# MTR_1_0.net
KiCad netlist of a schematic drawn in EAGLE
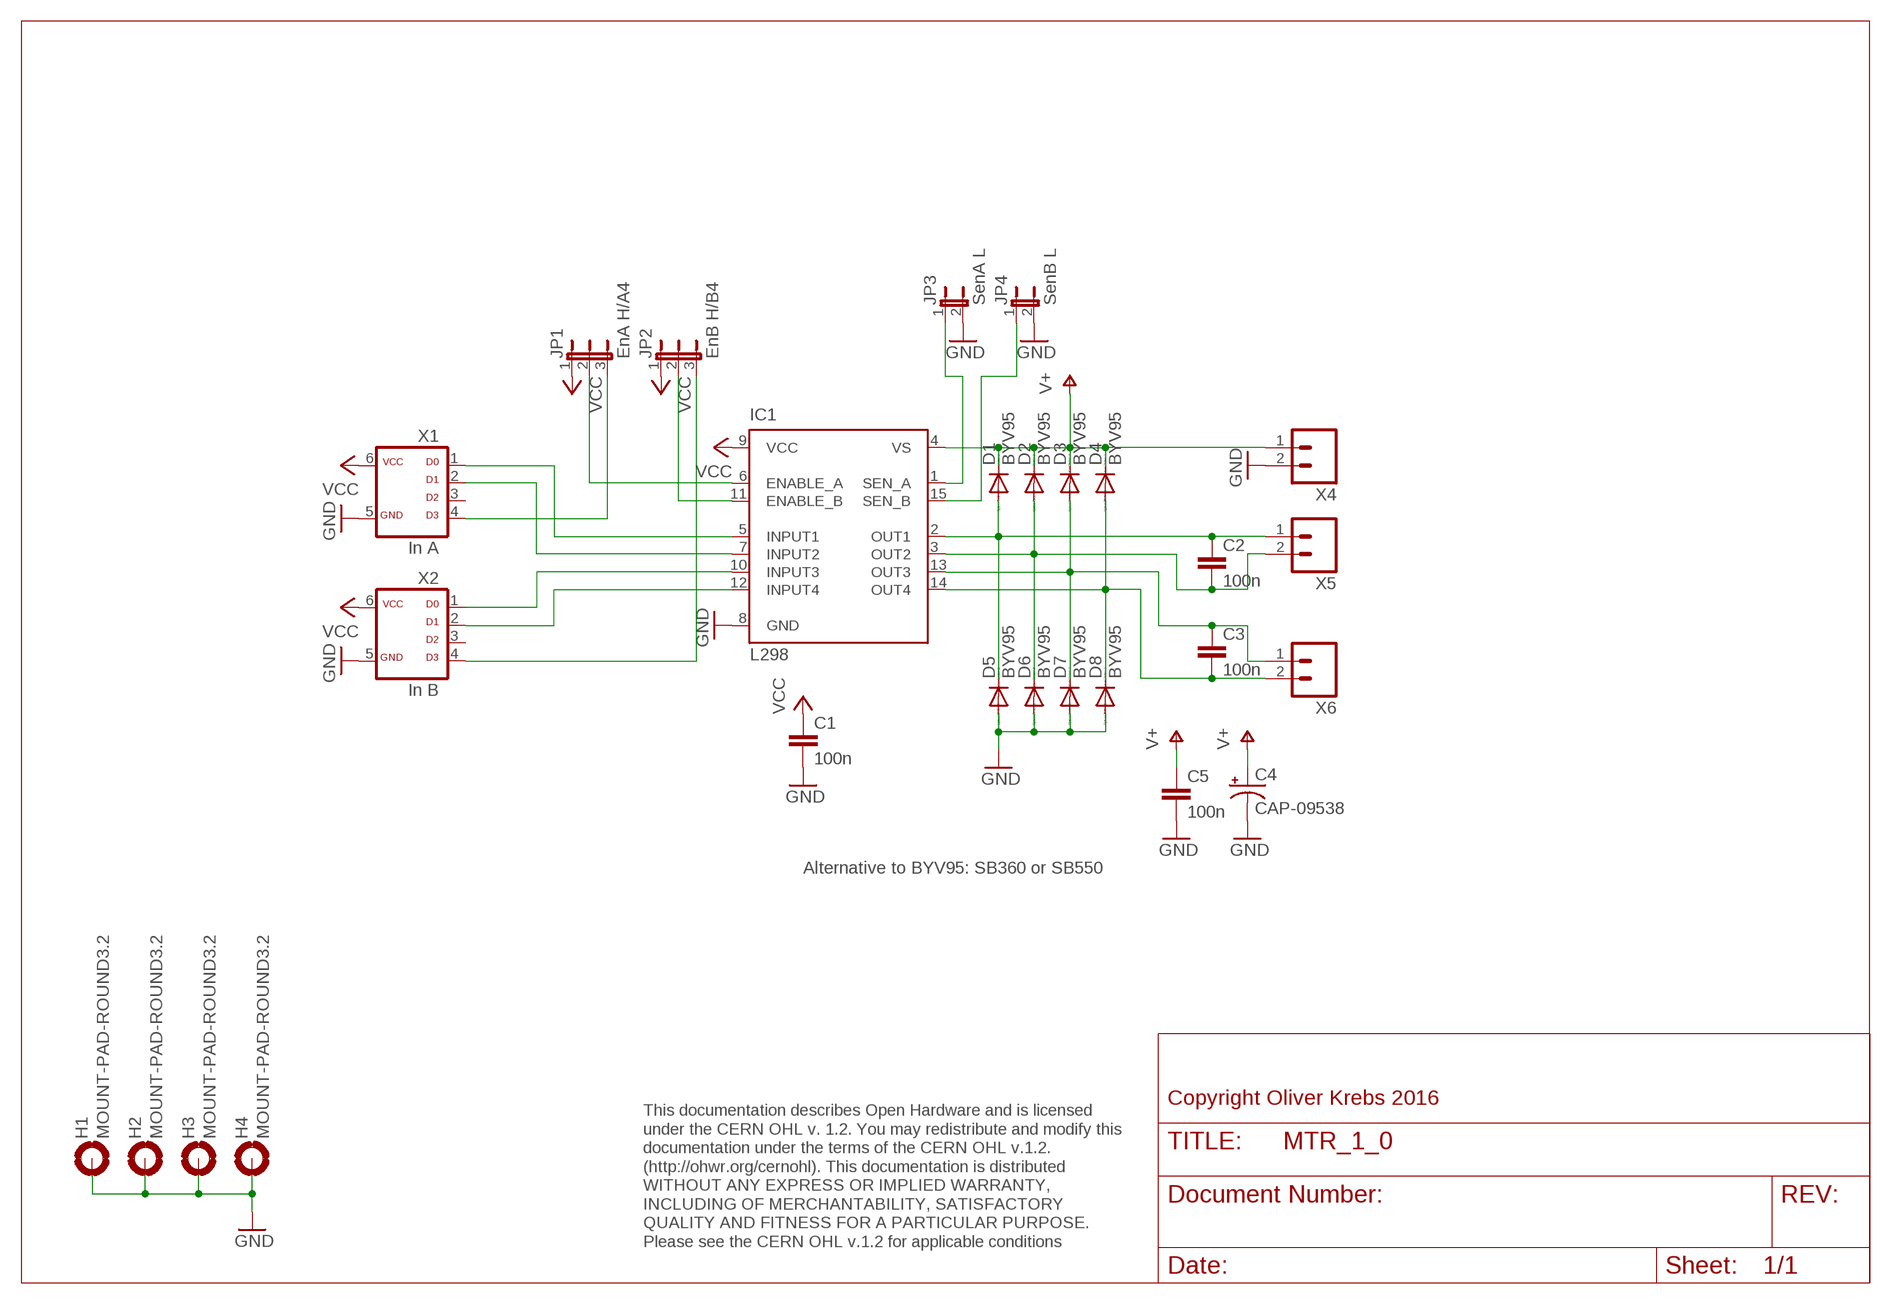
[diagram p0: schematic, sheet 1]

(export (version "E")
  (design (tool "Eeschema 10.0.6"))
  (components
    (comp (ref "C1")
      (value "100n")
      (footprint "eagle-import:C050-025X075")
      (libsource (lib "eagle-import") (part "C-EU050-025X075"))
    )
    (comp (ref "C2")
      (value "100n")
      (footprint "eagle-import:C050-025X075")
      (libsource (lib "eagle-import") (part "C-EU050-025X075"))
    )
    (comp (ref "C3")
      (value "100n")
      (footprint "eagle-import:C050-025X075")
      (libsource (lib "eagle-import") (part "C-EU050-025X075"))
    )
    (comp (ref "C4")
      (value "CAP-09538")
      (footprint "eagle-import:CPOL-RADIAL-1000UF-25V")
      (libsource (lib "eagle-import") (part "1000UF-25V(PTH)"))
    )
    (comp (ref "C5")
      (value "100n")
      (footprint "eagle-import:C050-025X075")
      (libsource (lib "eagle-import") (part "C-EU050-025X075"))
    )
    (comp (ref "D1")
      (value "BYV95")
      (footprint "eagle-import:SOD57-10")
      (libsource (lib "eagle-import") (part "BYV95"))
    )
    (comp (ref "D2")
      (value "BYV95")
      (footprint "eagle-import:SOD57-10")
      (libsource (lib "eagle-import") (part "BYV95"))
    )
    (comp (ref "D3")
      (value "BYV95")
      (footprint "eagle-import:SOD57-10")
      (libsource (lib "eagle-import") (part "BYV95"))
    )
    (comp (ref "D4")
      (value "BYV95")
      (footprint "eagle-import:SOD57-10")
      (libsource (lib "eagle-import") (part "BYV95"))
    )
    (comp (ref "D5")
      (value "BYV95")
      (footprint "eagle-import:SOD57-10")
      (libsource (lib "eagle-import") (part "BYV95"))
    )
    (comp (ref "D6")
      (value "BYV95")
      (footprint "eagle-import:SOD57-10")
      (libsource (lib "eagle-import") (part "BYV95"))
    )
    (comp (ref "D7")
      (value "BYV95")
      (footprint "eagle-import:SOD57-10")
      (libsource (lib "eagle-import") (part "BYV95"))
    )
    (comp (ref "D8")
      (value "BYV95")
      (footprint "eagle-import:SOD57-10")
      (libsource (lib "eagle-import") (part "BYV95"))
    )
    (comp (ref "H1")
      (value "MOUNT-PAD-ROUND3.2")
      (footprint "eagle-import:3,2-PAD")
      (libsource (lib "eagle-import") (part "MOUNT-PAD-ROUND3.2"))
    )
    (comp (ref "H2")
      (value "MOUNT-PAD-ROUND3.2")
      (footprint "eagle-import:3,2-PAD")
      (libsource (lib "eagle-import") (part "MOUNT-PAD-ROUND3.2"))
    )
    (comp (ref "H3")
      (value "MOUNT-PAD-ROUND3.2")
      (footprint "eagle-import:3,2-PAD")
      (libsource (lib "eagle-import") (part "MOUNT-PAD-ROUND3.2"))
    )
    (comp (ref "H4")
      (value "MOUNT-PAD-ROUND3.2")
      (footprint "eagle-import:3,2-PAD")
      (libsource (lib "eagle-import") (part "MOUNT-PAD-ROUND3.2"))
    )
    (comp (ref "IC1")
      (value "L298")
      (footprint "eagle-import:MULTIWATT-15")
      (fields (field (name "MPN") "L298N"))
      (libsource (lib "eagle-import") (part "L298"))
    )
    (comp (ref "JP1")
      (value "EnA H/A4")
      (footprint "eagle-import:JP2-U")
      (libsource (lib "eagle-import") (part "JP2EJP2-U"))
    )
    (comp (ref "JP2")
      (value "EnB H/B4")
      (footprint "eagle-import:JP2-U")
      (libsource (lib "eagle-import") (part "JP2EJP2-U"))
    )
    (comp (ref "JP3")
      (value "SenA L")
      (footprint "eagle-import:JP1")
      (libsource (lib "eagle-import") (part "JP1E"))
    )
    (comp (ref "JP4")
      (value "SenB L")
      (footprint "eagle-import:JP1")
      (libsource (lib "eagle-import") (part "JP1E"))
    )
    (comp (ref "X1")
      (value "In A")
      (footprint "eagle-import:ML-6")
      (libsource (lib "eagle-import") (part "ML6D"))
    )
    (comp (ref "X2")
      (value "In B")
      (footprint "eagle-import:ML-6")
      (libsource (lib "eagle-import") (part "ML6D"))
    )
    (comp (ref "X4")
      (value "M021.3MM-5.08")
      (footprint "eagle-import:1X02_BIG_5.08")
      (libsource (lib "eagle-import") (part "M021.3MM-5.08"))
    )
    (comp (ref "X5")
      (value "M021.3MM-5.08")
      (footprint "eagle-import:1X02_BIG_5.08")
      (libsource (lib "eagle-import") (part "M021.3MM-5.08"))
    )
    (comp (ref "X6")
      (value "M021.3MM-5.08")
      (footprint "eagle-import:1X02_BIG_5.08")
      (libsource (lib "eagle-import") (part "M021.3MM-5.08"))
    )
  )
  (nets
    (net (code "1") (name "GND") (class "Default")
      (node (ref "C1") (pin "2") (pinfunction "2_2") (pintype "passive"))
      (node (ref "C4") (pin "-") (pinfunction "-_-") (pintype "passive"))
      (node (ref "C5") (pin "2") (pinfunction "2_2") (pintype "passive"))
      (node (ref "D5") (pin "A") (pinfunction "A_A") (pintype "passive"))
      (node (ref "D6") (pin "A") (pinfunction "A_A") (pintype "passive"))
      (node (ref "D7") (pin "A") (pinfunction "A_A") (pintype "passive"))
      (node (ref "D8") (pin "A") (pinfunction "A_A") (pintype "passive"))
      (node (ref "H1") (pin "B3,2") (pinfunction "MOUNT_B3,2") (pintype "passive"))
      (node (ref "H2") (pin "B3,2") (pinfunction "MOUNT_B3,2") (pintype "passive"))
      (node (ref "H3") (pin "B3,2") (pinfunction "MOUNT_B3,2") (pintype "passive"))
      (node (ref "H4") (pin "B3,2") (pinfunction "MOUNT_B3,2") (pintype "passive"))
      (node (ref "IC1") (pin "8") (pinfunction "GND_8") (pintype "power_in"))
      (node (ref "JP3") (pin "2") (pinfunction "2_2") (pintype "passive"))
      (node (ref "JP4") (pin "2") (pinfunction "2_2") (pintype "passive"))
      (node (ref "X1") (pin "5") (pinfunction "5_5") (pintype "passive"))
      (node (ref "X2") (pin "5") (pinfunction "5_5") (pintype "passive"))
      (node (ref "X4") (pin "2") (pinfunction "2_2") (pintype "passive"))
    )
    (net (code "2") (name "Net-(IC1-ENABLE_A)") (class "Default")
      (node (ref "IC1") (pin "6") (pinfunction "ENABLE_A_6") (pintype "input"))
      (node (ref "JP1") (pin "2") (pinfunction "2_2") (pintype "passive"))
    )
    (net (code "3") (name "Net-(IC1-ENABLE_B)") (class "Default")
      (node (ref "IC1") (pin "11") (pinfunction "ENABLE_B_11") (pintype "input"))
      (node (ref "JP2") (pin "2") (pinfunction "2_2") (pintype "passive"))
    )
    (net (code "4") (name "Net-(IC1-INPUT1)") (class "Default")
      (node (ref "IC1") (pin "5") (pinfunction "INPUT1_5") (pintype "input"))
      (node (ref "X1") (pin "1") (pinfunction "1_1") (pintype "passive"))
    )
    (net (code "5") (name "Net-(IC1-INPUT2)") (class "Default")
      (node (ref "IC1") (pin "7") (pinfunction "INPUT2_7") (pintype "input"))
      (node (ref "X1") (pin "2") (pinfunction "2_2") (pintype "passive"))
    )
    (net (code "6") (name "Net-(IC1-INPUT3)") (class "Default")
      (node (ref "IC1") (pin "10") (pinfunction "INPUT3_10") (pintype "input"))
      (node (ref "X2") (pin "1") (pinfunction "1_1") (pintype "passive"))
    )
    (net (code "7") (name "Net-(IC1-INPUT4)") (class "Default")
      (node (ref "IC1") (pin "12") (pinfunction "INPUT4_12") (pintype "input"))
      (node (ref "X2") (pin "2") (pinfunction "2_2") (pintype "passive"))
    )
    (net (code "8") (name "Net-(IC1-OUT1)") (class "Default")
      (node (ref "C2") (pin "1") (pinfunction "1_1") (pintype "passive"))
      (node (ref "D1") (pin "A") (pinfunction "A_A") (pintype "passive"))
      (node (ref "D5") (pin "C") (pinfunction "C_C") (pintype "passive"))
      (node (ref "IC1") (pin "2") (pinfunction "OUT1_2") (pintype "output"))
      (node (ref "X5") (pin "1") (pinfunction "1_1") (pintype "passive"))
    )
    (net (code "9") (name "Net-(IC1-OUT2)") (class "Default")
      (node (ref "C2") (pin "2") (pinfunction "2_2") (pintype "passive"))
      (node (ref "D2") (pin "A") (pinfunction "A_A") (pintype "passive"))
      (node (ref "D6") (pin "C") (pinfunction "C_C") (pintype "passive"))
      (node (ref "IC1") (pin "3") (pinfunction "OUT2_3") (pintype "output"))
      (node (ref "X5") (pin "2") (pinfunction "2_2") (pintype "passive"))
    )
    (net (code "10") (name "Net-(IC1-OUT3)") (class "Default")
      (node (ref "C3") (pin "1") (pinfunction "1_1") (pintype "passive"))
      (node (ref "D3") (pin "A") (pinfunction "A_A") (pintype "passive"))
      (node (ref "D7") (pin "C") (pinfunction "C_C") (pintype "passive"))
      (node (ref "IC1") (pin "13") (pinfunction "OUT3_13") (pintype "output"))
      (node (ref "X6") (pin "1") (pinfunction "1_1") (pintype "passive"))
    )
    (net (code "11") (name "Net-(IC1-OUT4)") (class "Default")
      (node (ref "C3") (pin "2") (pinfunction "2_2") (pintype "passive"))
      (node (ref "D4") (pin "A") (pinfunction "A_A") (pintype "passive"))
      (node (ref "D8") (pin "C") (pinfunction "C_C") (pintype "passive"))
      (node (ref "IC1") (pin "14") (pinfunction "OUT4_14") (pintype "output"))
      (node (ref "X6") (pin "2") (pinfunction "2_2") (pintype "passive"))
    )
    (net (code "12") (name "Net-(IC1-SEN_A)") (class "Default")
      (node (ref "IC1") (pin "1") (pinfunction "SEN_A_1") (pintype "input"))
      (node (ref "JP3") (pin "1") (pinfunction "1_1") (pintype "passive"))
    )
    (net (code "13") (name "Net-(IC1-SEN_B)") (class "Default")
      (node (ref "IC1") (pin "15") (pinfunction "SEN_B_15") (pintype "input"))
      (node (ref "JP4") (pin "1") (pinfunction "1_1") (pintype "passive"))
    )
    (net (code "14") (name "Net-(JP1-Pad3)") (class "Default")
      (node (ref "JP1") (pin "3") (pinfunction "3_3") (pintype "passive"))
      (node (ref "X1") (pin "4") (pinfunction "4_4") (pintype "passive"))
    )
    (net (code "15") (name "Net-(JP2-Pad3)") (class "Default")
      (node (ref "JP2") (pin "3") (pinfunction "3_3") (pintype "passive"))
      (node (ref "X2") (pin "4") (pinfunction "4_4") (pintype "passive"))
    )
    (net (code "16") (name "V+") (class "Default")
      (node (ref "C4") (pin "+") (pinfunction "+_+") (pintype "passive"))
      (node (ref "C5") (pin "1") (pinfunction "1_1") (pintype "passive"))
      (node (ref "D1") (pin "C") (pinfunction "C_C") (pintype "passive"))
      (node (ref "D2") (pin "C") (pinfunction "C_C") (pintype "passive"))
      (node (ref "D3") (pin "C") (pinfunction "C_C") (pintype "passive"))
      (node (ref "D4") (pin "C") (pinfunction "C_C") (pintype "passive"))
      (node (ref "IC1") (pin "4") (pinfunction "VS_4") (pintype "power_in"))
      (node (ref "X4") (pin "1") (pinfunction "1_1") (pintype "passive"))
    )
    (net (code "17") (name "VCC") (class "Default")
      (node (ref "C1") (pin "1") (pinfunction "1_1") (pintype "passive"))
      (node (ref "IC1") (pin "9") (pinfunction "VCC_9") (pintype "power_in"))
      (node (ref "JP1") (pin "1") (pinfunction "1_1") (pintype "passive"))
      (node (ref "JP2") (pin "1") (pinfunction "1_1") (pintype "passive"))
      (node (ref "X1") (pin "6") (pinfunction "6_6") (pintype "passive"))
      (node (ref "X2") (pin "6") (pinfunction "6_6") (pintype "passive"))
    )
    (net (code "18") (name "unconnected-(X1-Pad3)") (class "Default")
      (node (ref "X1") (pin "3") (pinfunction "3_3") (pintype "passive"))
    )
    (net (code "19") (name "unconnected-(X2-Pad3)") (class "Default")
      (node (ref "X2") (pin "3") (pinfunction "3_3") (pintype "passive"))
    )
  )
)
